# PiKVM_USB_Adapter_v1_6.net
KiCad netlist of a schematic drawn in EAGLE
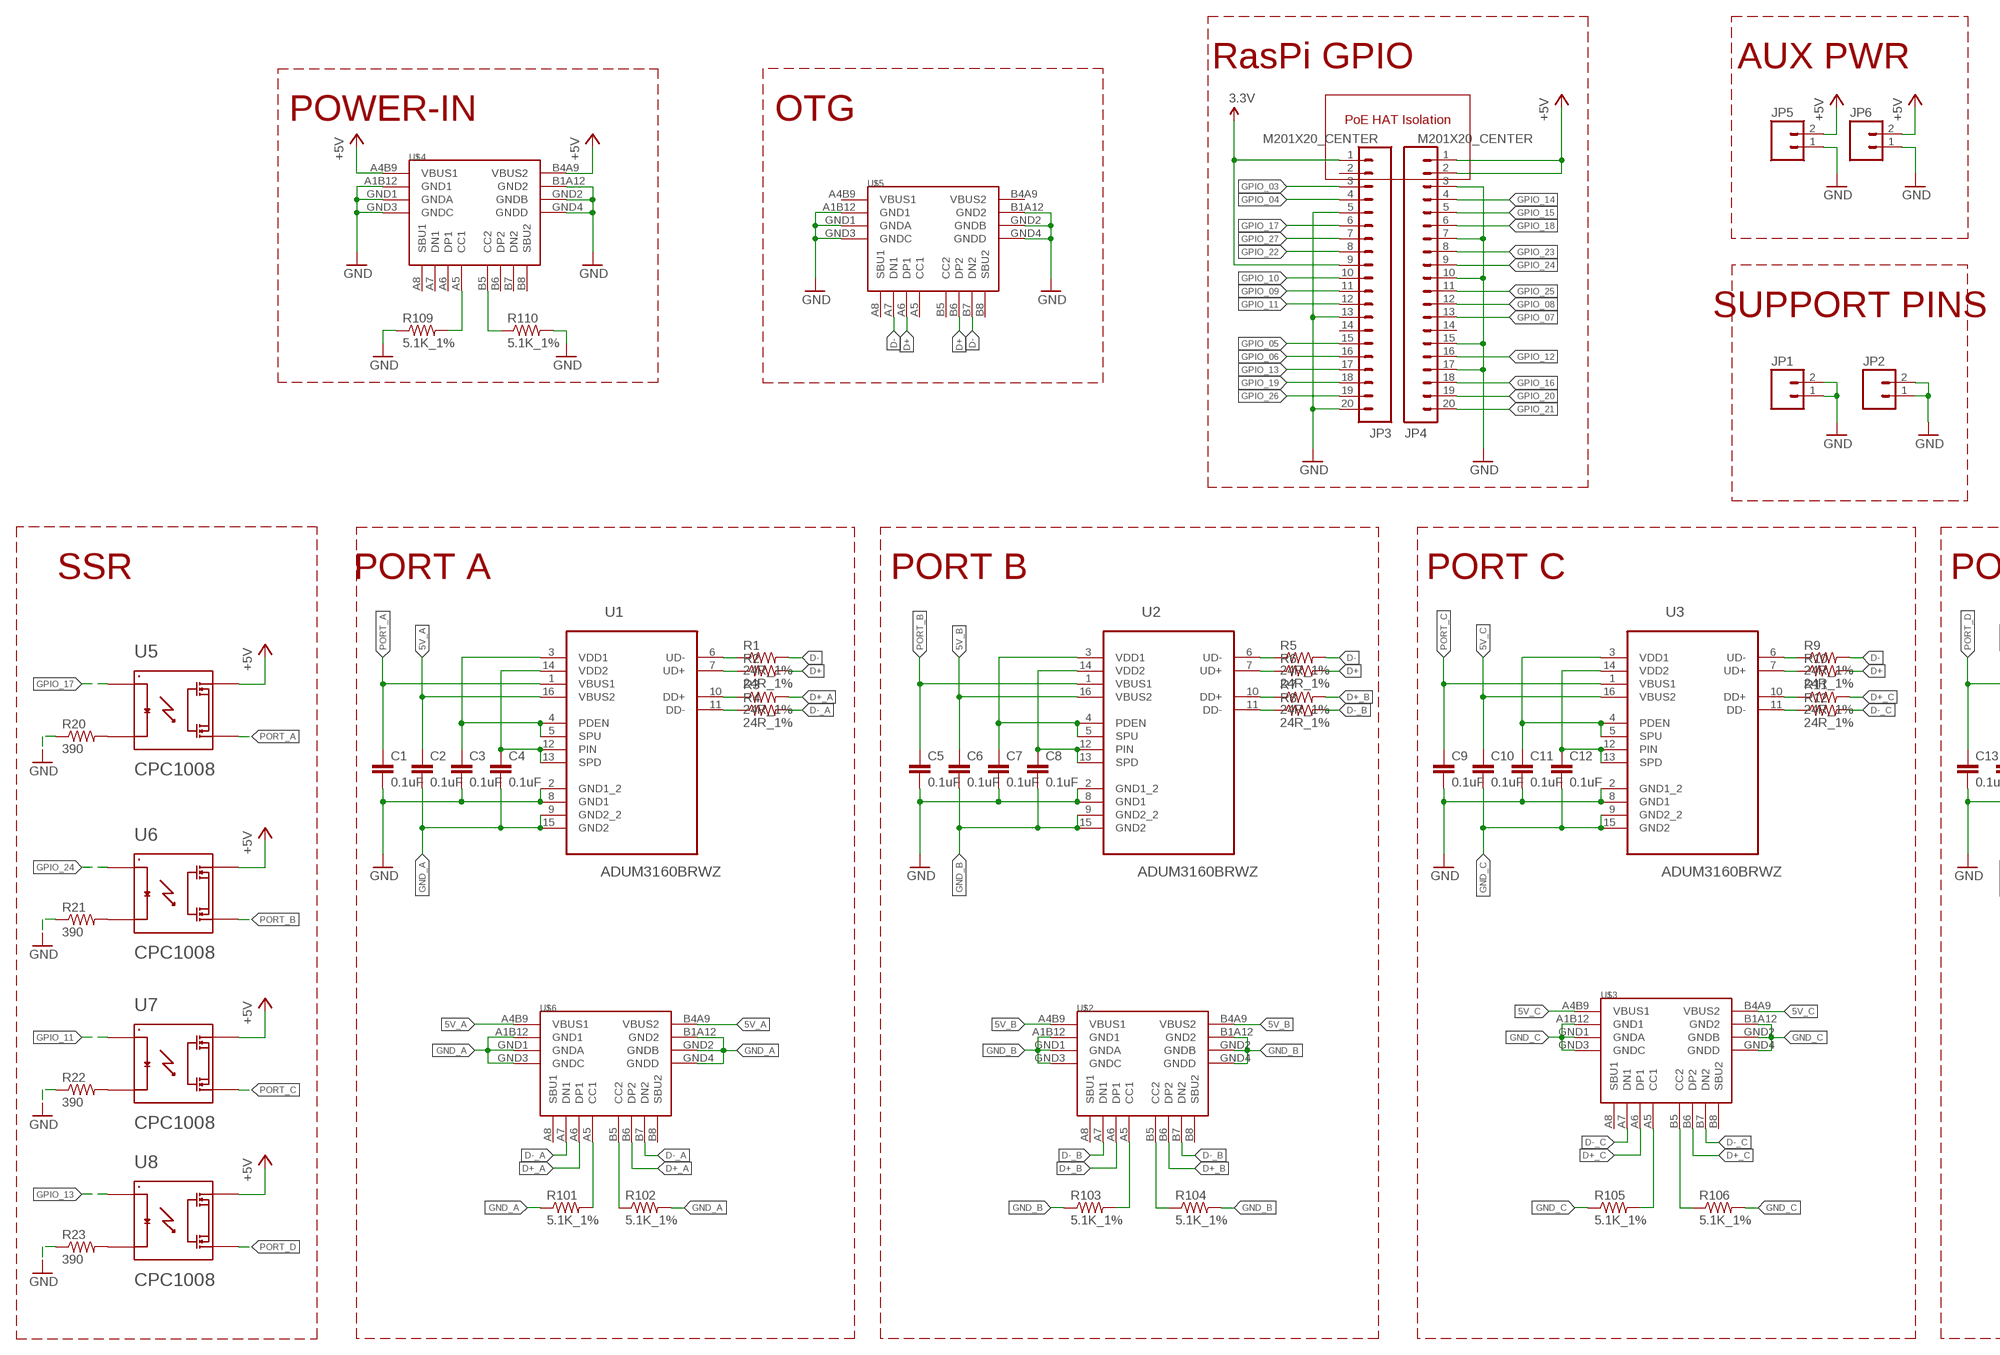
[diagram p0: schematic, sheet 1, part 1 of 2]
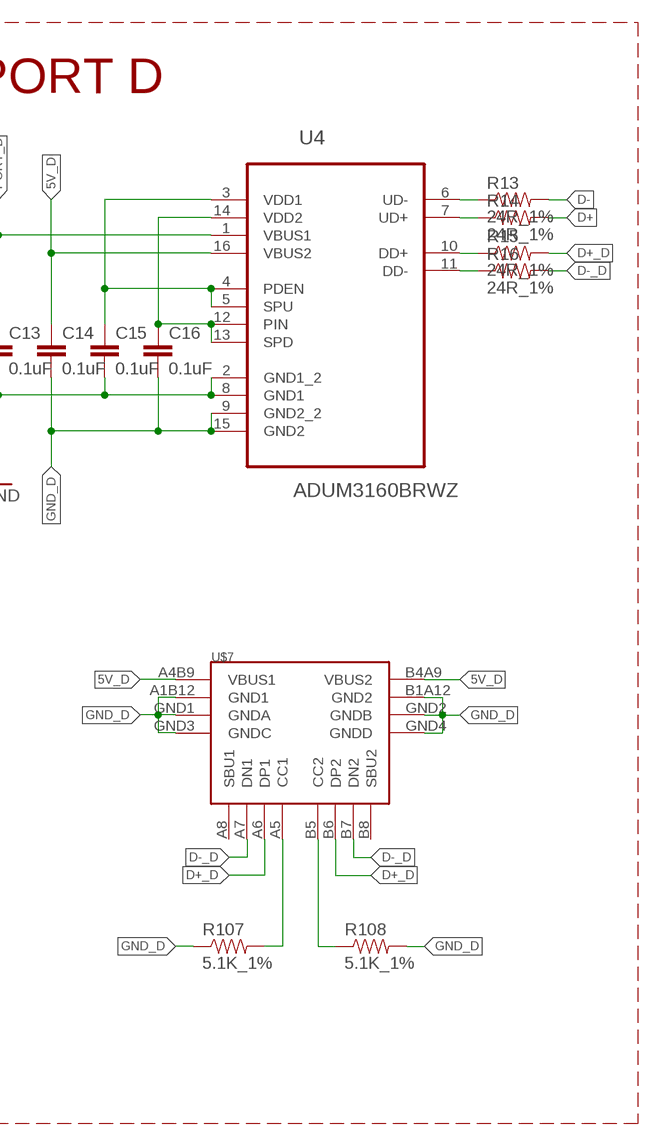
[diagram p1: schematic, sheet 1, part 2 of 2]

(export (version "E")
  (design (tool "Eeschema 10.0.6"))
  (components
    (comp (ref "C1")
      (value "0.1uF")
      (footprint "eagle-import:0805")
      (libsource (lib "eagle-import") (part "CAP0805"))
    )
    (comp (ref "C2")
      (value "0.1uF")
      (footprint "eagle-import:0805")
      (libsource (lib "eagle-import") (part "CAP0805"))
    )
    (comp (ref "C3")
      (value "0.1uF")
      (footprint "eagle-import:0805")
      (libsource (lib "eagle-import") (part "CAP0805"))
    )
    (comp (ref "C4")
      (value "0.1uF")
      (footprint "eagle-import:0805")
      (libsource (lib "eagle-import") (part "CAP0805"))
    )
    (comp (ref "C5")
      (value "0.1uF")
      (footprint "eagle-import:0805")
      (libsource (lib "eagle-import") (part "CAP0805"))
    )
    (comp (ref "C6")
      (value "0.1uF")
      (footprint "eagle-import:0805")
      (libsource (lib "eagle-import") (part "CAP0805"))
    )
    (comp (ref "C7")
      (value "0.1uF")
      (footprint "eagle-import:0805")
      (libsource (lib "eagle-import") (part "CAP0805"))
    )
    (comp (ref "C8")
      (value "0.1uF")
      (footprint "eagle-import:0805")
      (libsource (lib "eagle-import") (part "CAP0805"))
    )
    (comp (ref "C9")
      (value "0.1uF")
      (footprint "eagle-import:0805")
      (libsource (lib "eagle-import") (part "CAP0805"))
    )
    (comp (ref "C10")
      (value "0.1uF")
      (footprint "eagle-import:0805")
      (libsource (lib "eagle-import") (part "CAP0805"))
    )
    (comp (ref "C11")
      (value "0.1uF")
      (footprint "eagle-import:0805")
      (libsource (lib "eagle-import") (part "CAP0805"))
    )
    (comp (ref "C12")
      (value "0.1uF")
      (footprint "eagle-import:0805")
      (libsource (lib "eagle-import") (part "CAP0805"))
    )
    (comp (ref "C13")
      (value "0.1uF")
      (footprint "eagle-import:0805")
      (libsource (lib "eagle-import") (part "CAP0805"))
    )
    (comp (ref "C14")
      (value "0.1uF")
      (footprint "eagle-import:0805")
      (libsource (lib "eagle-import") (part "CAP0805"))
    )
    (comp (ref "C15")
      (value "0.1uF")
      (footprint "eagle-import:0805")
      (libsource (lib "eagle-import") (part "CAP0805"))
    )
    (comp (ref "C16")
      (value "0.1uF")
      (footprint "eagle-import:0805")
      (libsource (lib "eagle-import") (part "CAP0805"))
    )
    (comp (ref "JP1")
      (value "M02LOCK")
      (footprint "eagle-import:1X02_LOCK")
      (libsource (lib "eagle-import") (part "M02LOCK"))
    )
    (comp (ref "JP2")
      (value "M02LOCK")
      (footprint "eagle-import:1X02_LOCK")
      (libsource (lib "eagle-import") (part "M02LOCK"))
    )
    (comp (ref "JP3")
      (value "M201X20_CENTER")
      (footprint "eagle-import:1X20_CENTER")
      (libsource (lib "eagle-import") (part "M201X20_CENTER"))
    )
    (comp (ref "JP4")
      (value "M201X20_CENTER")
      (footprint "eagle-import:1X20_CENTER")
      (libsource (lib "eagle-import") (part "M201X20_CENTER"))
    )
    (comp (ref "JP5")
      (value "M02LOCK")
      (footprint "eagle-import:1X02_LOCK")
      (libsource (lib "eagle-import") (part "M02LOCK"))
    )
    (comp (ref "JP6")
      (value "M02LOCK")
      (footprint "eagle-import:1X02_LOCK")
      (libsource (lib "eagle-import") (part "M02LOCK"))
    )
    (comp (ref "R1")
      (value "24R_1%")
      (footprint "eagle-import:0805")
      (libsource (lib "eagle-import") (part "RESISTOR0805-RES"))
    )
    (comp (ref "R2")
      (value "24R_1%")
      (footprint "eagle-import:0805")
      (libsource (lib "eagle-import") (part "RESISTOR0805-RES"))
    )
    (comp (ref "R3")
      (value "24R_1%")
      (footprint "eagle-import:0805")
      (libsource (lib "eagle-import") (part "RESISTOR0805-RES"))
    )
    (comp (ref "R4")
      (value "24R_1%")
      (footprint "eagle-import:0805")
      (libsource (lib "eagle-import") (part "RESISTOR0805-RES"))
    )
    (comp (ref "R5")
      (value "24R_1%")
      (footprint "eagle-import:0805")
      (libsource (lib "eagle-import") (part "RESISTOR0805-RES"))
    )
    (comp (ref "R6")
      (value "24R_1%")
      (footprint "eagle-import:0805")
      (libsource (lib "eagle-import") (part "RESISTOR0805-RES"))
    )
    (comp (ref "R7")
      (value "24R_1%")
      (footprint "eagle-import:0805")
      (libsource (lib "eagle-import") (part "RESISTOR0805-RES"))
    )
    (comp (ref "R8")
      (value "24R_1%")
      (footprint "eagle-import:0805")
      (libsource (lib "eagle-import") (part "RESISTOR0805-RES"))
    )
    (comp (ref "R9")
      (value "24R_1%")
      (footprint "eagle-import:0805")
      (libsource (lib "eagle-import") (part "RESISTOR0805-RES"))
    )
    (comp (ref "R10")
      (value "24R_1%")
      (footprint "eagle-import:0805")
      (libsource (lib "eagle-import") (part "RESISTOR0805-RES"))
    )
    (comp (ref "R11")
      (value "24R_1%")
      (footprint "eagle-import:0805")
      (libsource (lib "eagle-import") (part "RESISTOR0805-RES"))
    )
    (comp (ref "R12")
      (value "24R_1%")
      (footprint "eagle-import:0805")
      (libsource (lib "eagle-import") (part "RESISTOR0805-RES"))
    )
    (comp (ref "R13")
      (value "24R_1%")
      (footprint "eagle-import:0805")
      (libsource (lib "eagle-import") (part "RESISTOR0805-RES"))
    )
    (comp (ref "R14")
      (value "24R_1%")
      (footprint "eagle-import:0805")
      (libsource (lib "eagle-import") (part "RESISTOR0805-RES"))
    )
    (comp (ref "R15")
      (value "24R_1%")
      (footprint "eagle-import:0805")
      (libsource (lib "eagle-import") (part "RESISTOR0805-RES"))
    )
    (comp (ref "R16")
      (value "24R_1%")
      (footprint "eagle-import:0805")
      (libsource (lib "eagle-import") (part "RESISTOR0805-RES"))
    )
    (comp (ref "R20")
      (value "390")
      (footprint "eagle-import:1206")
      (libsource (lib "eagle-import") (part "RESISTOR1206"))
    )
    (comp (ref "R21")
      (value "390")
      (footprint "eagle-import:1206")
      (libsource (lib "eagle-import") (part "RESISTOR1206"))
    )
    (comp (ref "R22")
      (value "390")
      (footprint "eagle-import:1206")
      (libsource (lib "eagle-import") (part "RESISTOR1206"))
    )
    (comp (ref "R23")
      (value "390")
      (footprint "eagle-import:1206")
      (libsource (lib "eagle-import") (part "RESISTOR1206"))
    )
    (comp (ref "R101")
      (value "5.1K_1%")
      (footprint "eagle-import:0805")
      (libsource (lib "eagle-import") (part "RESISTOR0805-RES"))
    )
    (comp (ref "R102")
      (value "5.1K_1%")
      (footprint "eagle-import:0805")
      (libsource (lib "eagle-import") (part "RESISTOR0805-RES"))
    )
    (comp (ref "R103")
      (value "5.1K_1%")
      (footprint "eagle-import:0805")
      (libsource (lib "eagle-import") (part "RESISTOR0805-RES"))
    )
    (comp (ref "R104")
      (value "5.1K_1%")
      (footprint "eagle-import:0805")
      (libsource (lib "eagle-import") (part "RESISTOR0805-RES"))
    )
    (comp (ref "R105")
      (value "5.1K_1%")
      (footprint "eagle-import:0805")
      (libsource (lib "eagle-import") (part "RESISTOR0805-RES"))
    )
    (comp (ref "R106")
      (value "5.1K_1%")
      (footprint "eagle-import:0805")
      (libsource (lib "eagle-import") (part "RESISTOR0805-RES"))
    )
    (comp (ref "R107")
      (value "5.1K_1%")
      (footprint "eagle-import:0805")
      (libsource (lib "eagle-import") (part "RESISTOR0805-RES"))
    )
    (comp (ref "R108")
      (value "5.1K_1%")
      (footprint "eagle-import:0805")
      (libsource (lib "eagle-import") (part "RESISTOR0805-RES"))
    )
    (comp (ref "R109")
      (value "5.1K_1%")
      (footprint "eagle-import:0805")
      (libsource (lib "eagle-import") (part "RESISTOR0805-RES"))
    )
    (comp (ref "R110")
      (value "5.1K_1%")
      (footprint "eagle-import:0805")
      (libsource (lib "eagle-import") (part "RESISTOR0805-RES"))
    )
    (comp (ref "U$2")
      (value "USB4110GFA")
      (footprint "eagle-import:GCT_USB4110GFA")
      (libsource (lib "eagle-import") (part "USB4110GFA"))
    )
    (comp (ref "U$3")
      (value "USB4110GFA")
      (footprint "eagle-import:GCT_USB4110GFA")
      (libsource (lib "eagle-import") (part "USB4110GFA"))
    )
    (comp (ref "U$4")
      (value "USB4110GFA")
      (footprint "eagle-import:GCT_USB4110GFA")
      (libsource (lib "eagle-import") (part "USB4110GFA"))
    )
    (comp (ref "U$5")
      (value "USB4110GFA")
      (footprint "eagle-import:GCT_USB4110GFA")
      (libsource (lib "eagle-import") (part "USB4110GFA"))
    )
    (comp (ref "U$6")
      (value "USB4110GFA")
      (footprint "eagle-import:GCT_USB4110GFA")
      (libsource (lib "eagle-import") (part "USB4110GFA"))
    )
    (comp (ref "U$7")
      (value "USB4110GFA")
      (footprint "eagle-import:GCT_USB4110GFA")
      (libsource (lib "eagle-import") (part "USB4110GFA"))
    )
    (comp (ref "U1")
      (value "ADUM3160BRWZ")
      (footprint "eagle-import:SOIC127P1032X265-16N")
      (libsource (lib "eagle-import") (part "ADUM3160BRWZ"))
    )
    (comp (ref "U2")
      (value "ADUM3160BRWZ")
      (footprint "eagle-import:SOIC127P1032X265-16N")
      (libsource (lib "eagle-import") (part "ADUM3160BRWZ"))
    )
    (comp (ref "U3")
      (value "ADUM3160BRWZ")
      (footprint "eagle-import:SOIC127P1032X265-16N")
      (libsource (lib "eagle-import") (part "ADUM3160BRWZ"))
    )
    (comp (ref "U4")
      (value "ADUM3160BRWZ")
      (footprint "eagle-import:SOIC127P1032X265-16N")
      (libsource (lib "eagle-import") (part "ADUM3160BRWZ"))
    )
    (comp (ref "U5")
      (value "CPC1008")
      (footprint "eagle-import:SOP-4")
      (libsource (lib "eagle-import") (part "CPC1008"))
    )
    (comp (ref "U6")
      (value "CPC1008")
      (footprint "eagle-import:SOP-4")
      (libsource (lib "eagle-import") (part "CPC1008"))
    )
    (comp (ref "U7")
      (value "CPC1008")
      (footprint "eagle-import:SOP-4")
      (libsource (lib "eagle-import") (part "CPC1008"))
    )
    (comp (ref "U8")
      (value "CPC1008")
      (footprint "eagle-import:SOP-4")
      (libsource (lib "eagle-import") (part "CPC1008"))
    )
  )
  (nets
    (net (code "1") (name "+5V") (class "Default")
      (node (ref "JP4") (pin "1") (pinfunction "1_1") (pintype "passive"))
      (node (ref "JP4") (pin "2") (pinfunction "2_2") (pintype "passive"))
      (node (ref "JP5") (pin "2") (pinfunction "2_2") (pintype "passive"))
      (node (ref "JP6") (pin "2") (pinfunction "2_2") (pintype "passive"))
      (node (ref "U$4") (pin "A4B9") (pinfunction "VBUS1_A4B9") (pintype "power_in"))
      (node (ref "U$4") (pin "B4A9") (pinfunction "VBUS2_B4A9") (pintype "power_in"))
      (node (ref "U5") (pin "P$4") (pinfunction "4_P$4") (pintype "bidirectional"))
      (node (ref "U6") (pin "P$4") (pinfunction "4_P$4") (pintype "bidirectional"))
      (node (ref "U7") (pin "P$4") (pinfunction "4_P$4") (pintype "bidirectional"))
      (node (ref "U8") (pin "P$4") (pinfunction "4_P$4") (pintype "bidirectional"))
    )
    (net (code "2") (name "/VBUS1") (class "Default")
      (node (ref "U$5") (pin "A4B9") (pinfunction "VBUS1_A4B9") (pintype "power_in"))
    )
    (net (code "3") (name "/VBUS2") (class "Default")
      (node (ref "U$5") (pin "B4A9") (pinfunction "VBUS2_B4A9") (pintype "power_in"))
    )
    (net (code "4") (name "3.3V") (class "Default")
      (node (ref "JP3") (pin "1") (pinfunction "1_1") (pintype "passive"))
      (node (ref "JP3") (pin "9") (pinfunction "9_9") (pintype "passive"))
    )
    (net (code "5") (name "5V_A") (class "Default")
      (node (ref "C2") (pin "1") (pinfunction "1_1") (pintype "passive"))
      (node (ref "U$6") (pin "A4B9") (pinfunction "VBUS1_A4B9") (pintype "power_in"))
      (node (ref "U$6") (pin "B4A9") (pinfunction "VBUS2_B4A9") (pintype "power_in"))
      (node (ref "U1") (pin "16") (pinfunction "VBUS2_16") (pintype "power_in"))
    )
    (net (code "6") (name "5V_B") (class "Default")
      (node (ref "C6") (pin "1") (pinfunction "1_1") (pintype "passive"))
      (node (ref "U$2") (pin "A4B9") (pinfunction "VBUS1_A4B9") (pintype "power_in"))
      (node (ref "U$2") (pin "B4A9") (pinfunction "VBUS2_B4A9") (pintype "power_in"))
      (node (ref "U2") (pin "16") (pinfunction "VBUS2_16") (pintype "power_in"))
    )
    (net (code "7") (name "5V_C") (class "Default")
      (node (ref "C10") (pin "1") (pinfunction "1_1") (pintype "passive"))
      (node (ref "U$3") (pin "A4B9") (pinfunction "VBUS1_A4B9") (pintype "power_in"))
      (node (ref "U$3") (pin "B4A9") (pinfunction "VBUS2_B4A9") (pintype "power_in"))
      (node (ref "U3") (pin "16") (pinfunction "VBUS2_16") (pintype "power_in"))
    )
    (net (code "8") (name "5V_D") (class "Default")
      (node (ref "C14") (pin "1") (pinfunction "1_1") (pintype "passive"))
      (node (ref "U$7") (pin "A4B9") (pinfunction "VBUS1_A4B9") (pintype "power_in"))
      (node (ref "U$7") (pin "B4A9") (pinfunction "VBUS2_B4A9") (pintype "power_in"))
      (node (ref "U4") (pin "16") (pinfunction "VBUS2_16") (pintype "power_in"))
    )
    (net (code "9") (name "D+") (class "Default")
      (node (ref "R10") (pin "2") (pinfunction "2_2") (pintype "passive"))
      (node (ref "R14") (pin "2") (pinfunction "2_2") (pintype "passive"))
      (node (ref "R2") (pin "2") (pinfunction "2_2") (pintype "passive"))
      (node (ref "R6") (pin "2") (pinfunction "2_2") (pintype "passive"))
      (node (ref "U$5") (pin "A6") (pinfunction "DP1_A6") (pintype "bidirectional"))
      (node (ref "U$5") (pin "B6") (pinfunction "DP2_B6") (pintype "bidirectional"))
    )
    (net (code "10") (name "D+_A") (class "Default")
      (node (ref "R3") (pin "2") (pinfunction "2_2") (pintype "passive"))
      (node (ref "U$6") (pin "A6") (pinfunction "DP1_A6") (pintype "bidirectional"))
      (node (ref "U$6") (pin "B6") (pinfunction "DP2_B6") (pintype "bidirectional"))
    )
    (net (code "11") (name "D+_B") (class "Default")
      (node (ref "R7") (pin "2") (pinfunction "2_2") (pintype "passive"))
      (node (ref "U$2") (pin "A6") (pinfunction "DP1_A6") (pintype "bidirectional"))
      (node (ref "U$2") (pin "B6") (pinfunction "DP2_B6") (pintype "bidirectional"))
    )
    (net (code "12") (name "D+_C") (class "Default")
      (node (ref "R11") (pin "2") (pinfunction "2_2") (pintype "passive"))
      (node (ref "U$3") (pin "A6") (pinfunction "DP1_A6") (pintype "bidirectional"))
      (node (ref "U$3") (pin "B6") (pinfunction "DP2_B6") (pintype "bidirectional"))
    )
    (net (code "13") (name "D+_D") (class "Default")
      (node (ref "R15") (pin "2") (pinfunction "2_2") (pintype "passive"))
      (node (ref "U$7") (pin "A6") (pinfunction "DP1_A6") (pintype "bidirectional"))
      (node (ref "U$7") (pin "B6") (pinfunction "DP2_B6") (pintype "bidirectional"))
    )
    (net (code "14") (name "D-") (class "Default")
      (node (ref "R1") (pin "2") (pinfunction "2_2") (pintype "passive"))
      (node (ref "R13") (pin "2") (pinfunction "2_2") (pintype "passive"))
      (node (ref "R5") (pin "2") (pinfunction "2_2") (pintype "passive"))
      (node (ref "R9") (pin "2") (pinfunction "2_2") (pintype "passive"))
      (node (ref "U$5") (pin "A7") (pinfunction "DN1_A7") (pintype "bidirectional"))
      (node (ref "U$5") (pin "B7") (pinfunction "DN2_B7") (pintype "bidirectional"))
    )
    (net (code "15") (name "D-_A") (class "Default")
      (node (ref "R4") (pin "2") (pinfunction "2_2") (pintype "passive"))
      (node (ref "U$6") (pin "A7") (pinfunction "DN1_A7") (pintype "bidirectional"))
      (node (ref "U$6") (pin "B7") (pinfunction "DN2_B7") (pintype "bidirectional"))
    )
    (net (code "16") (name "D-_B") (class "Default")
      (node (ref "R8") (pin "2") (pinfunction "2_2") (pintype "passive"))
      (node (ref "U$2") (pin "A7") (pinfunction "DN1_A7") (pintype "bidirectional"))
      (node (ref "U$2") (pin "B7") (pinfunction "DN2_B7") (pintype "bidirectional"))
    )
    (net (code "17") (name "D-_C") (class "Default")
      (node (ref "R12") (pin "2") (pinfunction "2_2") (pintype "passive"))
      (node (ref "U$3") (pin "A7") (pinfunction "DN1_A7") (pintype "bidirectional"))
      (node (ref "U$3") (pin "B7") (pinfunction "DN2_B7") (pintype "bidirectional"))
    )
    (net (code "18") (name "D-_D") (class "Default")
      (node (ref "R16") (pin "2") (pinfunction "2_2") (pintype "passive"))
      (node (ref "U$7") (pin "A7") (pinfunction "DN1_A7") (pintype "bidirectional"))
      (node (ref "U$7") (pin "B7") (pinfunction "DN2_B7") (pintype "bidirectional"))
    )
    (net (code "19") (name "GND") (class "Default")
      (node (ref "C1") (pin "2") (pinfunction "2_2") (pintype "passive"))
      (node (ref "C11") (pin "2") (pinfunction "2_2") (pintype "passive"))
      (node (ref "C13") (pin "2") (pinfunction "2_2") (pintype "passive"))
      (node (ref "C15") (pin "2") (pinfunction "2_2") (pintype "passive"))
      (node (ref "C3") (pin "2") (pinfunction "2_2") (pintype "passive"))
      (node (ref "C5") (pin "2") (pinfunction "2_2") (pintype "passive"))
      (node (ref "C7") (pin "2") (pinfunction "2_2") (pintype "passive"))
      (node (ref "C9") (pin "2") (pinfunction "2_2") (pintype "passive"))
      (node (ref "JP1") (pin "1") (pinfunction "1_1") (pintype "passive"))
      (node (ref "JP1") (pin "2") (pinfunction "2_2") (pintype "passive"))
      (node (ref "JP2") (pin "1") (pinfunction "1_1") (pintype "passive"))
      (node (ref "JP2") (pin "2") (pinfunction "2_2") (pintype "passive"))
      (node (ref "JP3") (pin "13") (pinfunction "13_13") (pintype "passive"))
      (node (ref "JP3") (pin "20") (pinfunction "20_20") (pintype "passive"))
      (node (ref "JP3") (pin "5") (pinfunction "5_5") (pintype "passive"))
      (node (ref "JP4") (pin "10") (pinfunction "10_10") (pintype "passive"))
      (node (ref "JP4") (pin "15") (pinfunction "15_15") (pintype "passive"))
      (node (ref "JP4") (pin "17") (pinfunction "17_17") (pintype "passive"))
      (node (ref "JP4") (pin "3") (pinfunction "3_3") (pintype "passive"))
      (node (ref "JP4") (pin "7") (pinfunction "7_7") (pintype "passive"))
      (node (ref "JP5") (pin "1") (pinfunction "1_1") (pintype "passive"))
      (node (ref "JP6") (pin "1") (pinfunction "1_1") (pintype "passive"))
      (node (ref "R109") (pin "1") (pinfunction "1_1") (pintype "passive"))
      (node (ref "R110") (pin "2") (pinfunction "2_2") (pintype "passive"))
      (node (ref "R20") (pin "1") (pinfunction "1_1") (pintype "passive"))
      (node (ref "R21") (pin "1") (pinfunction "1_1") (pintype "passive"))
      (node (ref "R22") (pin "1") (pinfunction "1_1") (pintype "passive"))
      (node (ref "R23") (pin "1") (pinfunction "1_1") (pintype "passive"))
      (node (ref "U$4") (pin "A1B12") (pinfunction "GND1_A1B12") (pintype "power_in"))
      (node (ref "U$4") (pin "B1A12") (pinfunction "GND2_B1A12") (pintype "power_in"))
      (node (ref "U$4") (pin "GND1") (pinfunction "GNDA_GND1") (pintype "power_in"))
      (node (ref "U$4") (pin "GND2") (pinfunction "GNDB_GND2") (pintype "power_in"))
      (node (ref "U$4") (pin "GND3") (pinfunction "GNDC_GND3") (pintype "power_in"))
      (node (ref "U$4") (pin "GND4") (pinfunction "GNDD_GND4") (pintype "power_in"))
      (node (ref "U$5") (pin "A1B12") (pinfunction "GND1_A1B12") (pintype "power_in"))
      (node (ref "U$5") (pin "B1A12") (pinfunction "GND2_B1A12") (pintype "power_in"))
      (node (ref "U$5") (pin "GND1") (pinfunction "GNDA_GND1") (pintype "power_in"))
      (node (ref "U$5") (pin "GND2") (pinfunction "GNDB_GND2") (pintype "power_in"))
      (node (ref "U$5") (pin "GND3") (pinfunction "GNDC_GND3") (pintype "power_in"))
      (node (ref "U$5") (pin "GND4") (pinfunction "GNDD_GND4") (pintype "power_in"))
      (node (ref "U1") (pin "2") (pinfunction "GND1_2_2") (pintype "passive"))
      (node (ref "U1") (pin "8") (pinfunction "GND1_8") (pintype "passive"))
      (node (ref "U2") (pin "2") (pinfunction "GND1_2_2") (pintype "passive"))
      (node (ref "U2") (pin "8") (pinfunction "GND1_8") (pintype "passive"))
      (node (ref "U3") (pin "2") (pinfunction "GND1_2_2") (pintype "passive"))
      (node (ref "U3") (pin "8") (pinfunction "GND1_8") (pintype "passive"))
      (node (ref "U4") (pin "2") (pinfunction "GND1_2_2") (pintype "passive"))
      (node (ref "U4") (pin "8") (pinfunction "GND1_8") (pintype "passive"))
    )
    (net (code "20") (name "GND_A") (class "Default")
      (node (ref "C2") (pin "2") (pinfunction "2_2") (pintype "passive"))
      (node (ref "C4") (pin "2") (pinfunction "2_2") (pintype "passive"))
      (node (ref "R101") (pin "1") (pinfunction "1_1") (pintype "passive"))
      (node (ref "R102") (pin "2") (pinfunction "2_2") (pintype "passive"))
      (node (ref "U$6") (pin "A1B12") (pinfunction "GND1_A1B12") (pintype "power_in"))
      (node (ref "U$6") (pin "B1A12") (pinfunction "GND2_B1A12") (pintype "power_in"))
      (node (ref "U$6") (pin "GND1") (pinfunction "GNDA_GND1") (pintype "power_in"))
      (node (ref "U$6") (pin "GND2") (pinfunction "GNDB_GND2") (pintype "power_in"))
      (node (ref "U$6") (pin "GND3") (pinfunction "GNDC_GND3") (pintype "power_in"))
      (node (ref "U$6") (pin "GND4") (pinfunction "GNDD_GND4") (pintype "power_in"))
      (node (ref "U1") (pin "15") (pinfunction "GND2_15") (pintype "passive"))
      (node (ref "U1") (pin "9") (pinfunction "GND2_2_9") (pintype "passive"))
    )
    (net (code "21") (name "GND_B") (class "Default")
      (node (ref "C6") (pin "2") (pinfunction "2_2") (pintype "passive"))
      (node (ref "C8") (pin "2") (pinfunction "2_2") (pintype "passive"))
      (node (ref "R103") (pin "1") (pinfunction "1_1") (pintype "passive"))
      (node (ref "R104") (pin "2") (pinfunction "2_2") (pintype "passive"))
      (node (ref "U$2") (pin "A1B12") (pinfunction "GND1_A1B12") (pintype "power_in"))
      (node (ref "U$2") (pin "B1A12") (pinfunction "GND2_B1A12") (pintype "power_in"))
      (node (ref "U$2") (pin "GND1") (pinfunction "GNDA_GND1") (pintype "power_in"))
      (node (ref "U$2") (pin "GND2") (pinfunction "GNDB_GND2") (pintype "power_in"))
      (node (ref "U$2") (pin "GND3") (pinfunction "GNDC_GND3") (pintype "power_in"))
      (node (ref "U$2") (pin "GND4") (pinfunction "GNDD_GND4") (pintype "power_in"))
      (node (ref "U2") (pin "15") (pinfunction "GND2_15") (pintype "passive"))
      (node (ref "U2") (pin "9") (pinfunction "GND2_2_9") (pintype "passive"))
    )
    (net (code "22") (name "GND_C") (class "Default")
      (node (ref "C10") (pin "2") (pinfunction "2_2") (pintype "passive"))
      (node (ref "C12") (pin "2") (pinfunction "2_2") (pintype "passive"))
      (node (ref "R105") (pin "1") (pinfunction "1_1") (pintype "passive"))
      (node (ref "R106") (pin "2") (pinfunction "2_2") (pintype "passive"))
      (node (ref "U$3") (pin "A1B12") (pinfunction "GND1_A1B12") (pintype "power_in"))
      (node (ref "U$3") (pin "B1A12") (pinfunction "GND2_B1A12") (pintype "power_in"))
      (node (ref "U$3") (pin "GND1") (pinfunction "GNDA_GND1") (pintype "power_in"))
      (node (ref "U$3") (pin "GND2") (pinfunction "GNDB_GND2") (pintype "power_in"))
      (node (ref "U$3") (pin "GND3") (pinfunction "GNDC_GND3") (pintype "power_in"))
      (node (ref "U$3") (pin "GND4") (pinfunction "GNDD_GND4") (pintype "power_in"))
      (node (ref "U3") (pin "15") (pinfunction "GND2_15") (pintype "passive"))
      (node (ref "U3") (pin "9") (pinfunction "GND2_2_9") (pintype "passive"))
    )
    (net (code "23") (name "GND_D") (class "Default")
      (node (ref "C14") (pin "2") (pinfunction "2_2") (pintype "passive"))
      (node (ref "C16") (pin "2") (pinfunction "2_2") (pintype "passive"))
      (node (ref "R107") (pin "1") (pinfunction "1_1") (pintype "passive"))
      (node (ref "R108") (pin "2") (pinfunction "2_2") (pintype "passive"))
      (node (ref "U$7") (pin "A1B12") (pinfunction "GND1_A1B12") (pintype "power_in"))
      (node (ref "U$7") (pin "B1A12") (pinfunction "GND2_B1A12") (pintype "power_in"))
      (node (ref "U$7") (pin "GND1") (pinfunction "GNDA_GND1") (pintype "power_in"))
      (node (ref "U$7") (pin "GND2") (pinfunction "GNDB_GND2") (pintype "power_in"))
      (node (ref "U$7") (pin "GND3") (pinfunction "GNDC_GND3") (pintype "power_in"))
      (node (ref "U$7") (pin "GND4") (pinfunction "GNDD_GND4") (pintype "power_in"))
      (node (ref "U4") (pin "15") (pinfunction "GND2_15") (pintype "passive"))
      (node (ref "U4") (pin "9") (pinfunction "GND2_2_9") (pintype "passive"))
    )
    (net (code "24") (name "GPIO_03") (class "Default")
      (node (ref "JP3") (pin "3") (pinfunction "3_3") (pintype "passive"))
    )
    (net (code "25") (name "GPIO_04") (class "Default")
      (node (ref "JP3") (pin "4") (pinfunction "4_4") (pintype "passive"))
    )
    (net (code "26") (name "GPIO_05") (class "Default")
      (node (ref "JP3") (pin "15") (pinfunction "15_15") (pintype "passive"))
    )
    (net (code "27") (name "GPIO_06") (class "Default")
      (node (ref "JP3") (pin "16") (pinfunction "16_16") (pintype "passive"))
    )
    (net (code "28") (name "GPIO_07") (class "Default")
      (node (ref "JP4") (pin "13") (pinfunction "13_13") (pintype "passive"))
    )
    (net (code "29") (name "GPIO_08") (class "Default")
      (node (ref "JP4") (pin "12") (pinfunction "12_12") (pintype "passive"))
    )
    (net (code "30") (name "GPIO_09") (class "Default")
      (node (ref "JP3") (pin "11") (pinfunction "11_11") (pintype "passive"))
    )
    (net (code "31") (name "GPIO_10") (class "Default")
      (node (ref "JP3") (pin "10") (pinfunction "10_10") (pintype "passive"))
    )
    (net (code "32") (name "GPIO_11") (class "Default")
      (node (ref "JP3") (pin "12") (pinfunction "12_12") (pintype "passive"))
      (node (ref "U7") (pin "P$1") (pinfunction "1_P$1") (pintype "bidirectional"))
    )
    (net (code "33") (name "GPIO_12") (class "Default")
      (node (ref "JP4") (pin "16") (pinfunction "16_16") (pintype "passive"))
    )
    (net (code "34") (name "GPIO_13") (class "Default")
      (node (ref "JP3") (pin "17") (pinfunction "17_17") (pintype "passive"))
      (node (ref "U8") (pin "P$1") (pinfunction "1_P$1") (pintype "bidirectional"))
    )
    (net (code "35") (name "GPIO_14") (class "Default")
      (node (ref "JP4") (pin "4") (pinfunction "4_4") (pintype "passive"))
    )
    (net (code "36") (name "GPIO_15") (class "Default")
      (node (ref "JP4") (pin "5") (pinfunction "5_5") (pintype "passive"))
    )
    (net (code "37") (name "GPIO_16") (class "Default")
      (node (ref "JP4") (pin "18") (pinfunction "18_18") (pintype "passive"))
    )
    (net (code "38") (name "GPIO_17") (class "Default")
      (node (ref "JP3") (pin "6") (pinfunction "6_6") (pintype "passive"))
      (node (ref "U5") (pin "P$1") (pinfunction "1_P$1") (pintype "bidirectional"))
    )
    (net (code "39") (name "GPIO_18") (class "Default")
      (node (ref "JP4") (pin "6") (pinfunction "6_6") (pintype "passive"))
    )
    (net (code "40") (name "GPIO_19") (class "Default")
      (node (ref "JP3") (pin "18") (pinfunction "18_18") (pintype "passive"))
    )
    (net (code "41") (name "GPIO_20") (class "Default")
      (node (ref "JP4") (pin "19") (pinfunction "19_19") (pintype "passive"))
    )
    (net (code "42") (name "GPIO_21") (class "Default")
      (node (ref "JP4") (pin "20") (pinfunction "20_20") (pintype "passive"))
    )
    (net (code "43") (name "GPIO_22") (class "Default")
      (node (ref "JP3") (pin "8") (pinfunction "8_8") (pintype "passive"))
    )
    (net (code "44") (name "GPIO_23") (class "Default")
      (node (ref "JP4") (pin "8") (pinfunction "8_8") (pintype "passive"))
    )
    (net (code "45") (name "GPIO_24") (class "Default")
      (node (ref "JP4") (pin "9") (pinfunction "9_9") (pintype "passive"))
      (node (ref "U6") (pin "P$1") (pinfunction "1_P$1") (pintype "bidirectional"))
    )
    (net (code "46") (name "GPIO_25") (class "Default")
      (node (ref "JP4") (pin "11") (pinfunction "11_11") (pintype "passive"))
    )
    (net (code "47") (name "GPIO_26") (class "Default")
      (node (ref "JP3") (pin "19") (pinfunction "19_19") (pintype "passive"))
    )
    (net (code "48") (name "GPIO_27") (class "Default")
      (node (ref "JP3") (pin "7") (pinfunction "7_7") (pintype "passive"))
    )
    (net (code "49") (name "Net-(U$2-CC1)") (class "Default")
      (node (ref "R103") (pin "2") (pinfunction "2_2") (pintype "passive"))
      (node (ref "U$2") (pin "A5") (pinfunction "CC1_A5") (pintype "bidirectional"))
    )
    (net (code "50") (name "Net-(U$2-CC2)") (class "Default")
      (node (ref "R104") (pin "1") (pinfunction "1_1") (pintype "passive"))
      (node (ref "U$2") (pin "B5") (pinfunction "CC2_B5") (pintype "bidirectional"))
    )
    (net (code "51") (name "Net-(U$3-CC1)") (class "Default")
      (node (ref "R105") (pin "2") (pinfunction "2_2") (pintype "passive"))
      (node (ref "U$3") (pin "A5") (pinfunction "CC1_A5") (pintype "bidirectional"))
    )
    (net (code "52") (name "Net-(U$3-CC2)") (class "Default")
      (node (ref "R106") (pin "1") (pinfunction "1_1") (pintype "passive"))
      (node (ref "U$3") (pin "B5") (pinfunction "CC2_B5") (pintype "bidirectional"))
    )
    (net (code "53") (name "Net-(U$4-CC1)") (class "Default")
      (node (ref "R109") (pin "2") (pinfunction "2_2") (pintype "passive"))
      (node (ref "U$4") (pin "A5") (pinfunction "CC1_A5") (pintype "bidirectional"))
    )
    (net (code "54") (name "Net-(U$4-CC2)") (class "Default")
      (node (ref "R110") (pin "1") (pinfunction "1_1") (pintype "passive"))
      (node (ref "U$4") (pin "B5") (pinfunction "CC2_B5") (pintype "bidirectional"))
    )
    (net (code "55") (name "Net-(U$6-CC1)") (class "Default")
      (node (ref "R101") (pin "2") (pinfunction "2_2") (pintype "passive"))
      (node (ref "U$6") (pin "A5") (pinfunction "CC1_A5") (pintype "bidirectional"))
    )
    (net (code "56") (name "Net-(U$6-CC2)") (class "Default")
      (node (ref "R102") (pin "1") (pinfunction "1_1") (pintype "passive"))
      (node (ref "U$6") (pin "B5") (pinfunction "CC2_B5") (pintype "bidirectional"))
    )
    (net (code "57") (name "Net-(U$7-CC1)") (class "Default")
      (node (ref "R107") (pin "2") (pinfunction "2_2") (pintype "passive"))
      (node (ref "U$7") (pin "A5") (pinfunction "CC1_A5") (pintype "bidirectional"))
    )
    (net (code "58") (name "Net-(U$7-CC2)") (class "Default")
      (node (ref "R108") (pin "1") (pinfunction "1_1") (pintype "passive"))
      (node (ref "U$7") (pin "B5") (pinfunction "CC2_B5") (pintype "bidirectional"))
    )
    (net (code "59") (name "Net-(U1-DD+)") (class "Default")
      (node (ref "R3") (pin "1") (pinfunction "1_1") (pintype "passive"))
      (node (ref "U1") (pin "10") (pinfunction "DD+_10") (pintype "bidirectional"))
    )
    (net (code "60") (name "Net-(U1-DD-)") (class "Default")
      (node (ref "R4") (pin "1") (pinfunction "1_1") (pintype "passive"))
      (node (ref "U1") (pin "11") (pinfunction "DD-_11") (pintype "bidirectional"))
    )
    (net (code "61") (name "Net-(U1-PDEN)") (class "Default")
      (node (ref "C3") (pin "1") (pinfunction "1_1") (pintype "passive"))
      (node (ref "U1") (pin "3") (pinfunction "VDD1_3") (pintype "power_in"))
      (node (ref "U1") (pin "4") (pinfunction "PDEN_4") (pintype "input"))
      (node (ref "U1") (pin "5") (pinfunction "SPU_5") (pintype "input"))
    )
    (net (code "62") (name "Net-(U1-PIN)") (class "Default")
      (node (ref "C4") (pin "1") (pinfunction "1_1") (pintype "passive"))
      (node (ref "U1") (pin "12") (pinfunction "PIN_12") (pintype "input"))
      (node (ref "U1") (pin "13") (pinfunction "SPD_13") (pintype "input"))
      (node (ref "U1") (pin "14") (pinfunction "VDD2_14") (pintype "power_in"))
    )
    (net (code "63") (name "Net-(U1-UD+)") (class "Default")
      (node (ref "R2") (pin "1") (pinfunction "1_1") (pintype "passive"))
      (node (ref "U1") (pin "7") (pinfunction "UD+_7") (pintype "bidirectional"))
    )
    (net (code "64") (name "Net-(U1-UD-)") (class "Default")
      (node (ref "R1") (pin "1") (pinfunction "1_1") (pintype "passive"))
      (node (ref "U1") (pin "6") (pinfunction "UD-_6") (pintype "bidirectional"))
    )
    (net (code "65") (name "Net-(U2-DD+)") (class "Default")
      (node (ref "R7") (pin "1") (pinfunction "1_1") (pintype "passive"))
      (node (ref "U2") (pin "10") (pinfunction "DD+_10") (pintype "bidirectional"))
    )
    (net (code "66") (name "Net-(U2-DD-)") (class "Default")
      (node (ref "R8") (pin "1") (pinfunction "1_1") (pintype "passive"))
      (node (ref "U2") (pin "11") (pinfunction "DD-_11") (pintype "bidirectional"))
    )
    (net (code "67") (name "Net-(U2-PDEN)") (class "Default")
      (node (ref "C7") (pin "1") (pinfunction "1_1") (pintype "passive"))
      (node (ref "U2") (pin "3") (pinfunction "VDD1_3") (pintype "power_in"))
      (node (ref "U2") (pin "4") (pinfunction "PDEN_4") (pintype "input"))
      (node (ref "U2") (pin "5") (pinfunction "SPU_5") (pintype "input"))
    )
    (net (code "68") (name "Net-(U2-PIN)") (class "Default")
      (node (ref "C8") (pin "1") (pinfunction "1_1") (pintype "passive"))
      (node (ref "U2") (pin "12") (pinfunction "PIN_12") (pintype "input"))
      (node (ref "U2") (pin "13") (pinfunction "SPD_13") (pintype "input"))
      (node (ref "U2") (pin "14") (pinfunction "VDD2_14") (pintype "power_in"))
    )
    (net (code "69") (name "Net-(U2-UD+)") (class "Default")
      (node (ref "R6") (pin "1") (pinfunction "1_1") (pintype "passive"))
      (node (ref "U2") (pin "7") (pinfunction "UD+_7") (pintype "bidirectional"))
    )
    (net (code "70") (name "Net-(U2-UD-)") (class "Default")
      (node (ref "R5") (pin "1") (pinfunction "1_1") (pintype "passive"))
      (node (ref "U2") (pin "6") (pinfunction "UD-_6") (pintype "bidirectional"))
    )
    (net (code "71") (name "Net-(U3-DD+)") (class "Default")
      (node (ref "R11") (pin "1") (pinfunction "1_1") (pintype "passive"))
      (node (ref "U3") (pin "10") (pinfunction "DD+_10") (pintype "bidirectional"))
    )
    (net (code "72") (name "Net-(U3-DD-)") (class "Default")
      (node (ref "R12") (pin "1") (pinfunction "1_1") (pintype "passive"))
      (node (ref "U3") (pin "11") (pinfunction "DD-_11") (pintype "bidirectional"))
    )
    (net (code "73") (name "Net-(U3-PDEN)") (class "Default")
      (node (ref "C11") (pin "1") (pinfunction "1_1") (pintype "passive"))
      (node (ref "U3") (pin "3") (pinfunction "VDD1_3") (pintype "power_in"))
      (node (ref "U3") (pin "4") (pinfunction "PDEN_4") (pintype "input"))
      (node (ref "U3") (pin "5") (pinfunction "SPU_5") (pintype "input"))
    )
    (net (code "74") (name "Net-(U3-PIN)") (class "Default")
      (node (ref "C12") (pin "1") (pinfunction "1_1") (pintype "passive"))
      (node (ref "U3") (pin "12") (pinfunction "PIN_12") (pintype "input"))
      (node (ref "U3") (pin "13") (pinfunction "SPD_13") (pintype "input"))
      (node (ref "U3") (pin "14") (pinfunction "VDD2_14") (pintype "power_in"))
    )
    (net (code "75") (name "Net-(U3-UD+)") (class "Default")
      (node (ref "R10") (pin "1") (pinfunction "1_1") (pintype "passive"))
      (node (ref "U3") (pin "7") (pinfunction "UD+_7") (pintype "bidirectional"))
    )
    (net (code "76") (name "Net-(U3-UD-)") (class "Default")
      (node (ref "R9") (pin "1") (pinfunction "1_1") (pintype "passive"))
      (node (ref "U3") (pin "6") (pinfunction "UD-_6") (pintype "bidirectional"))
    )
    (net (code "77") (name "Net-(U4-DD+)") (class "Default")
      (node (ref "R15") (pin "1") (pinfunction "1_1") (pintype "passive"))
      (node (ref "U4") (pin "10") (pinfunction "DD+_10") (pintype "bidirectional"))
    )
    (net (code "78") (name "Net-(U4-DD-)") (class "Default")
      (node (ref "R16") (pin "1") (pinfunction "1_1") (pintype "passive"))
      (node (ref "U4") (pin "11") (pinfunction "DD-_11") (pintype "bidirectional"))
    )
    (net (code "79") (name "Net-(U4-PDEN)") (class "Default")
      (node (ref "C15") (pin "1") (pinfunction "1_1") (pintype "passive"))
      (node (ref "U4") (pin "3") (pinfunction "VDD1_3") (pintype "power_in"))
      (node (ref "U4") (pin "4") (pinfunction "PDEN_4") (pintype "input"))
      (node (ref "U4") (pin "5") (pinfunction "SPU_5") (pintype "input"))
    )
    (net (code "80") (name "Net-(U4-PIN)") (class "Default")
      (node (ref "C16") (pin "1") (pinfunction "1_1") (pintype "passive"))
      (node (ref "U4") (pin "12") (pinfunction "PIN_12") (pintype "input"))
      (node (ref "U4") (pin "13") (pinfunction "SPD_13") (pintype "input"))
      (node (ref "U4") (pin "14") (pinfunction "VDD2_14") (pintype "power_in"))
    )
    (net (code "81") (name "Net-(U4-UD+)") (class "Default")
      (node (ref "R14") (pin "1") (pinfunction "1_1") (pintype "passive"))
      (node (ref "U4") (pin "7") (pinfunction "UD+_7") (pintype "bidirectional"))
    )
    (net (code "82") (name "Net-(U4-UD-)") (class "Default")
      (node (ref "R13") (pin "1") (pinfunction "1_1") (pintype "passive"))
      (node (ref "U4") (pin "6") (pinfunction "UD-_6") (pintype "bidirectional"))
    )
    (net (code "83") (name "Net-(U5-2)") (class "Default")
      (node (ref "R20") (pin "2") (pinfunction "2_2") (pintype "passive"))
      (node (ref "U5") (pin "P$2") (pinfunction "2_P$2") (pintype "bidirectional"))
    )
    (net (code "84") (name "Net-(U6-2)") (class "Default")
      (node (ref "R21") (pin "2") (pinfunction "2_2") (pintype "passive"))
      (node (ref "U6") (pin "P$2") (pinfunction "2_P$2") (pintype "bidirectional"))
    )
    (net (code "85") (name "Net-(U7-2)") (class "Default")
      (node (ref "R22") (pin "2") (pinfunction "2_2") (pintype "passive"))
      (node (ref "U7") (pin "P$2") (pinfunction "2_P$2") (pintype "bidirectional"))
    )
    (net (code "86") (name "Net-(U8-2)") (class "Default")
      (node (ref "R23") (pin "2") (pinfunction "2_2") (pintype "passive"))
      (node (ref "U8") (pin "P$2") (pinfunction "2_P$2") (pintype "bidirectional"))
    )
    (net (code "87") (name "PORT_A") (class "Default")
      (node (ref "C1") (pin "1") (pinfunction "1_1") (pintype "passive"))
      (node (ref "U1") (pin "1") (pinfunction "VBUS1_1") (pintype "power_in"))
      (node (ref "U5") (pin "P$3") (pinfunction "3_P$3") (pintype "bidirectional"))
    )
    (net (code "88") (name "PORT_B") (class "Default")
      (node (ref "C5") (pin "1") (pinfunction "1_1") (pintype "passive"))
      (node (ref "U2") (pin "1") (pinfunction "VBUS1_1") (pintype "power_in"))
      (node (ref "U6") (pin "P$3") (pinfunction "3_P$3") (pintype "bidirectional"))
    )
    (net (code "89") (name "PORT_C") (class "Default")
      (node (ref "C9") (pin "1") (pinfunction "1_1") (pintype "passive"))
      (node (ref "U3") (pin "1") (pinfunction "VBUS1_1") (pintype "power_in"))
      (node (ref "U7") (pin "P$3") (pinfunction "3_P$3") (pintype "bidirectional"))
    )
    (net (code "90") (name "PORT_D") (class "Default")
      (node (ref "C13") (pin "1") (pinfunction "1_1") (pintype "passive"))
      (node (ref "U4") (pin "1") (pinfunction "VBUS1_1") (pintype "power_in"))
      (node (ref "U8") (pin "P$3") (pinfunction "3_P$3") (pintype "bidirectional"))
    )
    (net (code "91") (name "unconnected-(JP3-Pad2)") (class "Default")
      (node (ref "JP3") (pin "2") (pinfunction "2_2") (pintype "passive"))
    )
    (net (code "92") (name "unconnected-(JP3-Pad14)") (class "Default")
      (node (ref "JP3") (pin "14") (pinfunction "14_14") (pintype "passive"))
    )
    (net (code "93") (name "unconnected-(JP4-Pad14)") (class "Default")
      (node (ref "JP4") (pin "14") (pinfunction "14_14") (pintype "passive"))
    )
    (net (code "94") (name "unconnected-(U$2-SBU1-PadA8)") (class "Default")
      (node (ref "U$2") (pin "A8") (pinfunction "SBU1_A8") (pintype "bidirectional"))
    )
    (net (code "95") (name "unconnected-(U$2-SBU2-PadB8)") (class "Default")
      (node (ref "U$2") (pin "B8") (pinfunction "SBU2_B8") (pintype "bidirectional"))
    )
    (net (code "96") (name "unconnected-(U$3-SBU1-PadA8)") (class "Default")
      (node (ref "U$3") (pin "A8") (pinfunction "SBU1_A8") (pintype "bidirectional"))
    )
    (net (code "97") (name "unconnected-(U$3-SBU2-PadB8)") (class "Default")
      (node (ref "U$3") (pin "B8") (pinfunction "SBU2_B8") (pintype "bidirectional"))
    )
    (net (code "98") (name "unconnected-(U$4-DN1-PadA7)") (class "Default")
      (node (ref "U$4") (pin "A7") (pinfunction "DN1_A7") (pintype "bidirectional"))
    )
    (net (code "99") (name "unconnected-(U$4-DN2-PadB7)") (class "Default")
      (node (ref "U$4") (pin "B7") (pinfunction "DN2_B7") (pintype "bidirectional"))
    )
    (net (code "100") (name "unconnected-(U$4-DP1-PadA6)") (class "Default")
      (node (ref "U$4") (pin "A6") (pinfunction "DP1_A6") (pintype "bidirectional"))
    )
    (net (code "101") (name "unconnected-(U$4-DP2-PadB6)") (class "Default")
      (node (ref "U$4") (pin "B6") (pinfunction "DP2_B6") (pintype "bidirectional"))
    )
    (net (code "102") (name "unconnected-(U$4-SBU1-PadA8)") (class "Default")
      (node (ref "U$4") (pin "A8") (pinfunction "SBU1_A8") (pintype "bidirectional"))
    )
    (net (code "103") (name "unconnected-(U$4-SBU2-PadB8)") (class "Default")
      (node (ref "U$4") (pin "B8") (pinfunction "SBU2_B8") (pintype "bidirectional"))
    )
    (net (code "104") (name "unconnected-(U$5-CC1-PadA5)") (class "Default")
      (node (ref "U$5") (pin "A5") (pinfunction "CC1_A5") (pintype "bidirectional"))
    )
    (net (code "105") (name "unconnected-(U$5-CC2-PadB5)") (class "Default")
      (node (ref "U$5") (pin "B5") (pinfunction "CC2_B5") (pintype "bidirectional"))
    )
    (net (code "106") (name "unconnected-(U$5-SBU1-PadA8)") (class "Default")
      (node (ref "U$5") (pin "A8") (pinfunction "SBU1_A8") (pintype "bidirectional"))
    )
    (net (code "107") (name "unconnected-(U$5-SBU2-PadB8)") (class "Default")
      (node (ref "U$5") (pin "B8") (pinfunction "SBU2_B8") (pintype "bidirectional"))
    )
    (net (code "108") (name "unconnected-(U$6-SBU1-PadA8)") (class "Default")
      (node (ref "U$6") (pin "A8") (pinfunction "SBU1_A8") (pintype "bidirectional"))
    )
    (net (code "109") (name "unconnected-(U$6-SBU2-PadB8)") (class "Default")
      (node (ref "U$6") (pin "B8") (pinfunction "SBU2_B8") (pintype "bidirectional"))
    )
    (net (code "110") (name "unconnected-(U$7-SBU1-PadA8)") (class "Default")
      (node (ref "U$7") (pin "A8") (pinfunction "SBU1_A8") (pintype "bidirectional"))
    )
    (net (code "111") (name "unconnected-(U$7-SBU2-PadB8)") (class "Default")
      (node (ref "U$7") (pin "B8") (pinfunction "SBU2_B8") (pintype "bidirectional"))
    )
  )
)
